# SparkFun_Qwiic_Mini_Human_Presence_Senso.net
KiCad netlist of a schematic drawn in EAGLE
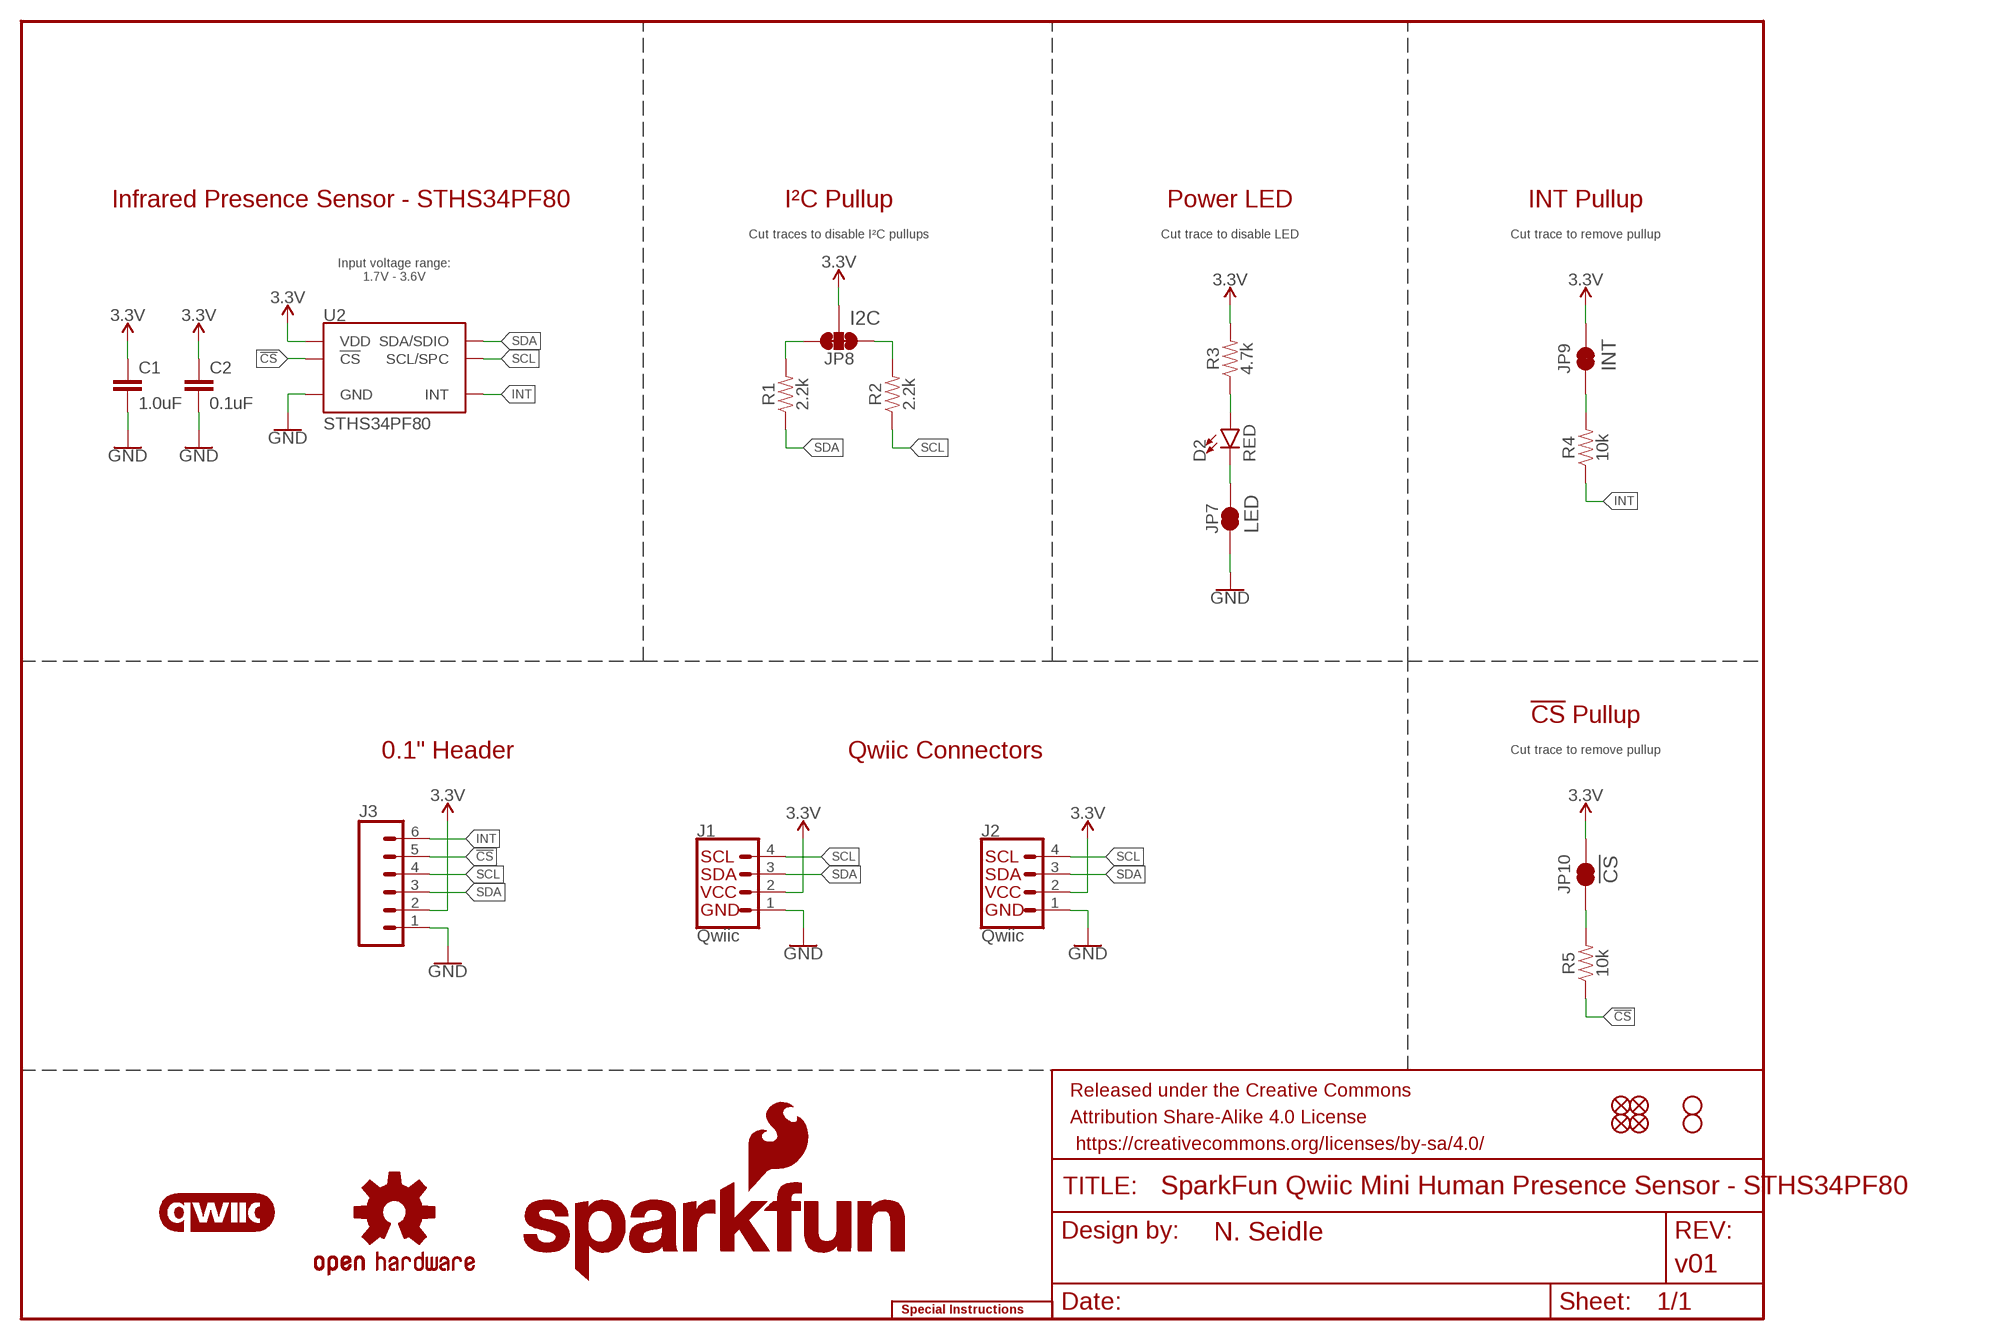
[diagram p0: schematic, sheet 1]

(export (version "E")
  (design (tool "Eeschema 10.0.6"))
  (components
    (comp (ref "C1")
      (value "1.0uF")
      (footprint "eagle-import:0603")
      (libsource (lib "eagle-import") (part "1.0UF-0603-16V-10%"))
    )
    (comp (ref "C2")
      (value "0.1uF")
      (footprint "eagle-import:0603")
      (libsource (lib "eagle-import") (part "0.1UF-0603-25V-(+80/-20%)"))
    )
    (comp (ref "D2")
      (value "RED")
      (footprint "eagle-import:LED-0603")
      (libsource (lib "eagle-import") (part "LED-RED_0603-KB"))
    )
    (comp (ref "FRAME1")
      (value "FRAME-LETTER")
      (footprint "eagle-import:CREATIVE_COMMONS")
      (fields (field (name "DESIGNER") "N. Seidle") (field (name "REV") "v01"))
      (libsource (lib "eagle-import") (part "FRAME-LETTER"))
    )
    (comp (ref "J1")
      (value "Qwiic")
      (footprint "eagle-import:JST04_1MM_RA")
      (libsource (lib "eagle-import") (part "QWIIC_CONNECTORJS-1MM"))
    )
    (comp (ref "J2")
      (value "Qwiic")
      (footprint "eagle-import:JST04_1MM_RA")
      (libsource (lib "eagle-import") (part "QWIIC_CONNECTORJS-1MM"))
    )
    (comp (ref "J3")
      (value "CONN_06NO_SILK_FEMALE_PTH")
      (footprint "eagle-import:1X06_NO_SILK")
      (libsource (lib "eagle-import") (part "CONN_06NO_SILK_FEMALE_PTH"))
    )
    (comp (ref "JP1")
      (value "FIDUCIALUFIDUCIAL")
      (footprint "eagle-import:FIDUCIAL-MICRO")
      (libsource (lib "eagle-import") (part "FIDUCIALUFIDUCIAL"))
    )
    (comp (ref "JP2")
      (value "FIDUCIALUFIDUCIAL")
      (footprint "eagle-import:FIDUCIAL-MICRO")
      (libsource (lib "eagle-import") (part "FIDUCIALUFIDUCIAL"))
    )
    (comp (ref "JP3")
      (value "STAND-OFF")
      (footprint "eagle-import:STAND-OFF")
      (libsource (lib "eagle-import") (part "STAND-OFF"))
    )
    (comp (ref "JP4")
      (value "STAND-OFF")
      (footprint "eagle-import:STAND-OFF")
      (libsource (lib "eagle-import") (part "STAND-OFF"))
    )
    (comp (ref "JP5")
      (value "FIDUCIALUFIDUCIAL")
      (footprint "eagle-import:FIDUCIAL-MICRO")
      (libsource (lib "eagle-import") (part "FIDUCIALUFIDUCIAL"))
    )
    (comp (ref "JP6")
      (value "FIDUCIALUFIDUCIAL")
      (footprint "eagle-import:FIDUCIAL-MICRO")
      (libsource (lib "eagle-import") (part "FIDUCIALUFIDUCIAL"))
    )
    (comp (ref "JP7")
      (value "JUMPER-SMT_2_NC_TRACE_SILK")
      (footprint "eagle-import:SMT-JUMPER_2_NC_TRACE_SILK")
      (libsource (lib "eagle-import") (part "JUMPER-SMT_2_NC_TRACE_SILK"))
    )
    (comp (ref "JP8")
      (value "JUMPER-SMT_3_2-NC_TRACE_SILK")
      (footprint "eagle-import:SMT-JUMPER_3_2-NC_TRACE_SILK")
      (libsource (lib "eagle-import") (part "JUMPER-SMT_3_2-NC_TRACE_SILK"))
    )
    (comp (ref "JP9")
      (value "JUMPER-SMT_2_NC_TRACE_SILK")
      (footprint "eagle-import:SMT-JUMPER_2_NC_TRACE_SILK")
      (libsource (lib "eagle-import") (part "JUMPER-SMT_2_NC_TRACE_SILK"))
    )
    (comp (ref "JP10")
      (value "JUMPER-SMT_2_NC_TRACE_SILK")
      (footprint "eagle-import:SMT-JUMPER_2_NC_TRACE_SILK")
      (libsource (lib "eagle-import") (part "JUMPER-SMT_2_NC_TRACE_SILK"))
    )
    (comp (ref "LOGO1")
      (value "OSHW-LOGOS")
      (footprint "eagle-import:OSHW-LOGO-S")
      (libsource (lib "eagle-import") (part "OSHW-LOGOS"))
    )
    (comp (ref "LOGO2")
      (value "SFE_LOGO_NAME_FLAME7_MM")
      (footprint "eagle-import:SFE_LOGO_NAME_FLAME_7MM")
      (libsource (lib "eagle-import") (part "SFE_LOGO_NAME_FLAME7_MM"))
    )
    (comp (ref "LOGO3")
      (value "QWIIC_LOGO_CONNECTOR")
      (footprint "eagle-import:QWIIC_5.5MM")
      (libsource (lib "eagle-import") (part "QWIIC_LOGO_CONNECTOR"))
    )
    (comp (ref "LOGO4")
      (value "SFE_LOGO_NAME5_MM")
      (footprint "eagle-import:SFE_LOGO_NAME_5MM")
      (libsource (lib "eagle-import") (part "SFE_LOGO_NAME5_MM"))
    )
    (comp (ref "LOGO5")
      (value "SPECIAL_INSTRUCTIONS-ORDERING")
      (footprint "eagle-import:ORDERING_INSTRUCTIONS")
      (libsource (lib "eagle-import") (part "SPECIAL_INSTRUCTIONS-ORDERING"))
    )
    (comp (ref "LOGO6")
      (value "SFE_LOGO_FLAME.1_INCH")
      (footprint "eagle-import:SFE_LOGO_FLAME_.1")
      (libsource (lib "eagle-import") (part "SFE_LOGO_FLAME.1_INCH"))
    )
    (comp (ref "R1")
      (value "2.2k")
      (footprint "eagle-import:0603")
      (libsource (lib "eagle-import") (part "2.2KOHM-0603-1/10W-1%"))
    )
    (comp (ref "R2")
      (value "2.2k")
      (footprint "eagle-import:0603")
      (libsource (lib "eagle-import") (part "2.2KOHM-0603-1/10W-1%"))
    )
    (comp (ref "R3")
      (value "4.7k")
      (footprint "eagle-import:0603")
      (libsource (lib "eagle-import") (part "4.7KOHM-0603-1/10W-1%"))
    )
    (comp (ref "R4")
      (value "10k")
      (footprint "eagle-import:0603")
      (libsource (lib "eagle-import") (part "10KOHM-0603-1/10W-1%"))
    )
    (comp (ref "R5")
      (value "10k")
      (footprint "eagle-import:0603")
      (libsource (lib "eagle-import") (part "10KOHM-0603-1/10W-1%"))
    )
    (comp (ref "U2")
      (value "STHS34PF80")
      (footprint "eagle-import:OLGA-10L")
      (libsource (lib "eagle-import") (part "STHS34PF80"))
    )
  )
  (nets
    (net (code "1") (name "/~{CS}") (class "Default")
      (node (ref "J3") (pin "5") (pinfunction "5_5") (pintype "passive"))
      (node (ref "R5") (pin "1") (pinfunction "1_1") (pintype "passive"))
      (node (ref "U2") (pin "3") (pinfunction "~{CS}_3") (pintype "input"))
    )
    (net (code "2") (name "3.3V") (class "Default")
      (node (ref "C1") (pin "1") (pinfunction "1_1") (pintype "passive"))
      (node (ref "C2") (pin "1") (pinfunction "1_1") (pintype "passive"))
      (node (ref "J1") (pin "2") (pinfunction "2_2") (pintype "power_in"))
      (node (ref "J2") (pin "2") (pinfunction "2_2") (pintype "power_in"))
      (node (ref "J3") (pin "2") (pinfunction "2_2") (pintype "passive"))
      (node (ref "JP10") (pin "2") (pinfunction "2_2") (pintype "passive"))
      (node (ref "JP8") (pin "2") (pinfunction "2_2") (pintype "passive"))
      (node (ref "JP9") (pin "2") (pinfunction "2_2") (pintype "passive"))
      (node (ref "R3") (pin "2") (pinfunction "2_2") (pintype "passive"))
      (node (ref "U2") (pin "6") (pinfunction "VDD_6") (pintype "power_in"))
      (node (ref "U2") (pin "9") (pinfunction "VDD_9") (pintype "power_in"))
    )
    (net (code "3") (name "GND") (class "Default")
      (node (ref "C1") (pin "2") (pinfunction "2_2") (pintype "passive"))
      (node (ref "C2") (pin "2") (pinfunction "2_2") (pintype "passive"))
      (node (ref "J1") (pin "1") (pinfunction "1_1") (pintype "power_in"))
      (node (ref "J2") (pin "1") (pinfunction "1_1") (pintype "power_in"))
      (node (ref "J3") (pin "1") (pinfunction "1_1") (pintype "passive"))
      (node (ref "JP7") (pin "1") (pinfunction "1_1") (pintype "passive"))
      (node (ref "U2") (pin "2") (pinfunction "GND_2") (pintype "power_in"))
      (node (ref "U2") (pin "7") (pinfunction "GND_7") (pintype "power_in"))
      (node (ref "U2") (pin "8") (pinfunction "GND_8") (pintype "power_in"))
    )
    (net (code "4") (name "INT") (class "Default")
      (node (ref "J3") (pin "6") (pinfunction "6_6") (pintype "passive"))
      (node (ref "R4") (pin "1") (pinfunction "1_1") (pintype "passive"))
      (node (ref "U2") (pin "10") (pinfunction "INT_10") (pintype "output"))
    )
    (net (code "5") (name "Net-(D2-PadA)") (class "Default")
      (node (ref "D2") (pin "A") (pinfunction "A_A") (pintype "passive"))
      (node (ref "R3") (pin "1") (pinfunction "1_1") (pintype "passive"))
    )
    (net (code "6") (name "Net-(D2-PadC)") (class "Default")
      (node (ref "D2") (pin "C") (pinfunction "C_C") (pintype "passive"))
      (node (ref "JP7") (pin "2") (pinfunction "2_2") (pintype "passive"))
    )
    (net (code "7") (name "Net-(JP8-Pad1)") (class "Default")
      (node (ref "JP8") (pin "1") (pinfunction "1_1") (pintype "passive"))
      (node (ref "R2") (pin "2") (pinfunction "2_2") (pintype "passive"))
    )
    (net (code "8") (name "Net-(JP8-Pad3)") (class "Default")
      (node (ref "JP8") (pin "3") (pinfunction "3_3") (pintype "passive"))
      (node (ref "R1") (pin "2") (pinfunction "2_2") (pintype "passive"))
    )
    (net (code "9") (name "Net-(JP9-Pad1)") (class "Default")
      (node (ref "JP9") (pin "1") (pinfunction "1_1") (pintype "passive"))
      (node (ref "R4") (pin "2") (pinfunction "2_2") (pintype "passive"))
    )
    (net (code "10") (name "Net-(JP10-Pad1)") (class "Default")
      (node (ref "JP10") (pin "1") (pinfunction "1_1") (pintype "passive"))
      (node (ref "R5") (pin "2") (pinfunction "2_2") (pintype "passive"))
    )
    (net (code "11") (name "SCL") (class "Default")
      (node (ref "J1") (pin "4") (pinfunction "4_4") (pintype "passive"))
      (node (ref "J2") (pin "4") (pinfunction "4_4") (pintype "passive"))
      (node (ref "J3") (pin "4") (pinfunction "4_4") (pintype "passive"))
      (node (ref "R2") (pin "1") (pinfunction "1_1") (pintype "passive"))
      (node (ref "U2") (pin "1") (pinfunction "SCL/SPC_1") (pintype "bidirectional"))
    )
    (net (code "12") (name "SDA") (class "Default")
      (node (ref "J1") (pin "3") (pinfunction "3_3") (pintype "passive"))
      (node (ref "J2") (pin "3") (pinfunction "3_3") (pintype "passive"))
      (node (ref "J3") (pin "3") (pinfunction "3_3") (pintype "passive"))
      (node (ref "R1") (pin "1") (pinfunction "1_1") (pintype "passive"))
      (node (ref "U2") (pin "4") (pinfunction "SDA/SDIO_4") (pintype "bidirectional"))
    )
  )
)
